# auxboxshield1_52.net
KiCad netlist of a schematic drawn in EAGLE
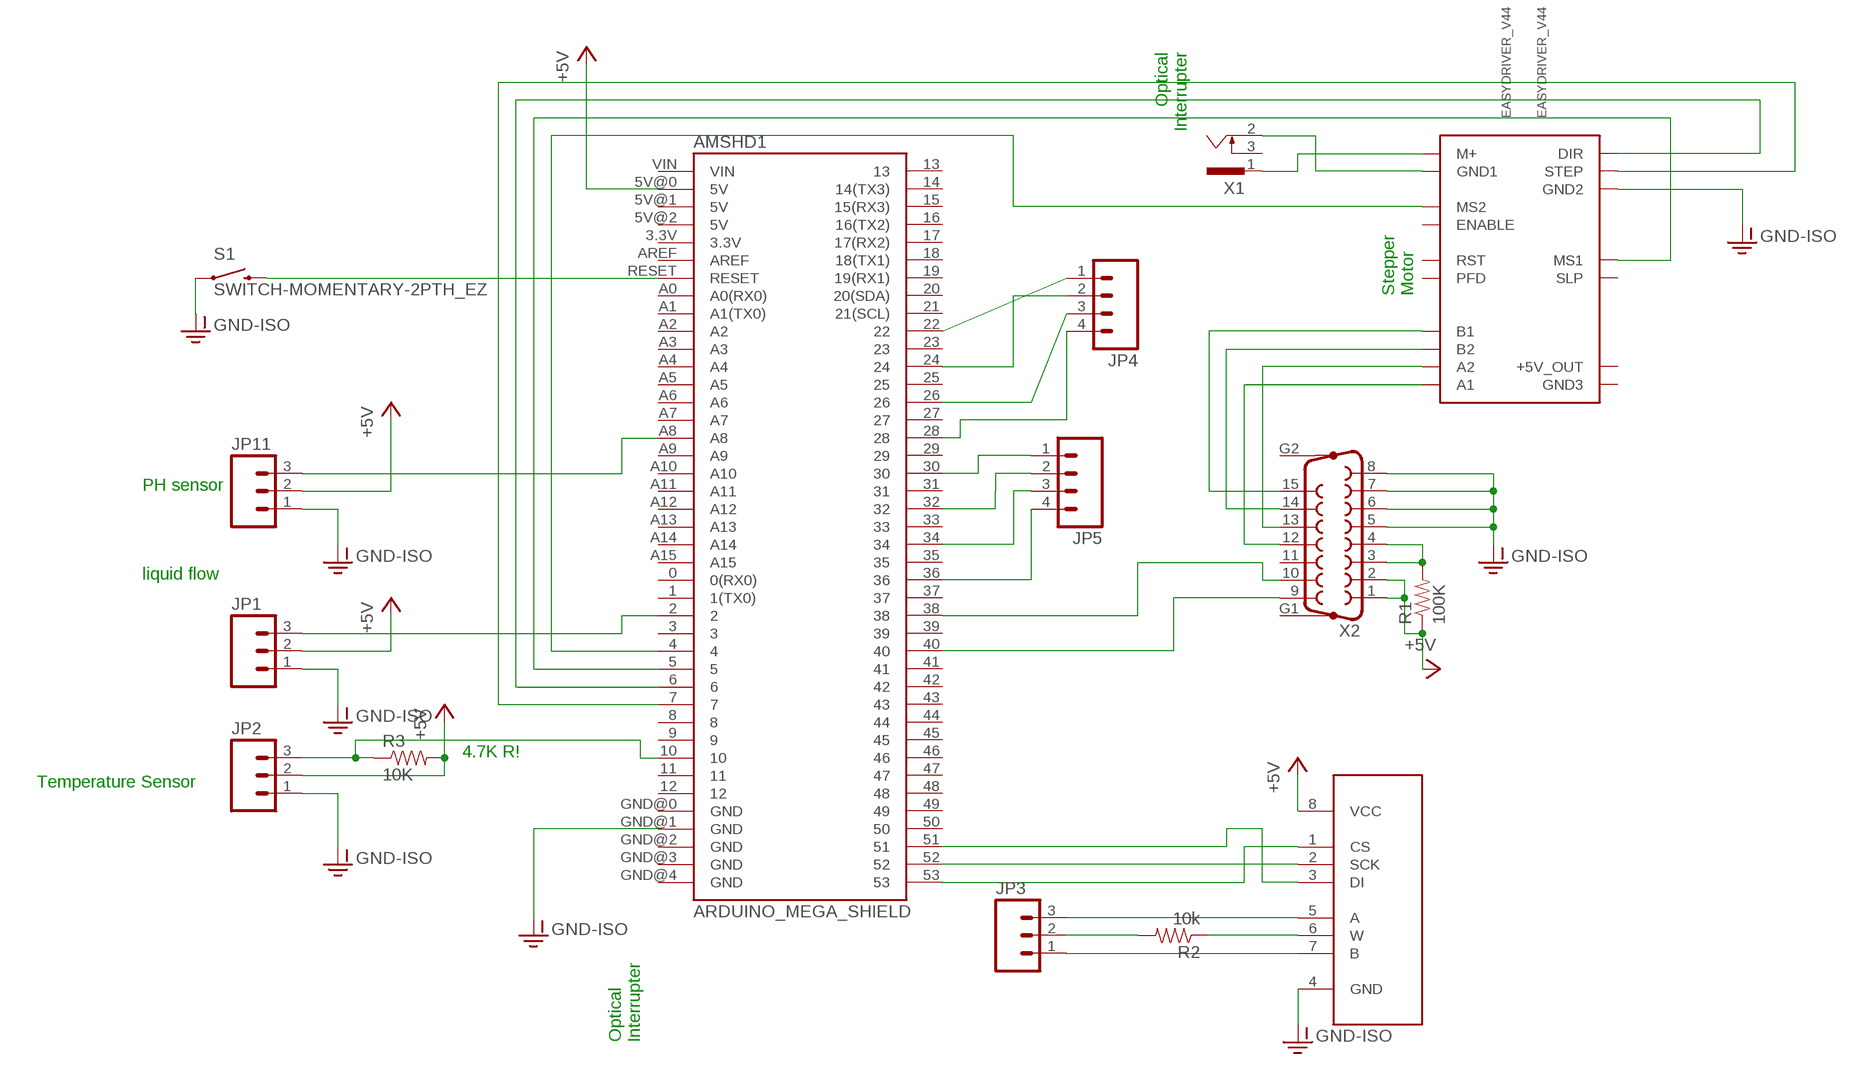
[diagram p0: schematic, sheet 1]

(export (version "E")
  (design (tool "Eeschema 10.0.6"))
  (components
    (comp (ref "AMSHD1")
      (value "ARDUINO_MEGA_SHIELD")
      (footprint "eagle-import:ARDUINO_MEGA_SHIELD")
      (libsource (lib "eagle-import") (part "ARDUINO_MEGA_SHIELD"))
    )
    (comp (ref "EASYDRIVER_V44")
      (value "EASYDRIVER_V44")
      (footprint "eagle-import:EASYDRIVER_V44")
      (libsource (lib "eagle-import") (part "EASYDRIVER_V44"))
    )
    (comp (ref "JP1")
      (value "M03POLAR")
      (footprint "eagle-import:MOLEX-1X3")
      (libsource (lib "eagle-import") (part "M03POLAR"))
    )
    (comp (ref "JP2")
      (value "M03POLAR")
      (footprint "eagle-import:MOLEX-1X3")
      (libsource (lib "eagle-import") (part "M03POLAR"))
    )
    (comp (ref "JP3")
      (value "M03POLAR")
      (footprint "eagle-import:MOLEX-1X3")
      (libsource (lib "eagle-import") (part "M03POLAR"))
    )
    (comp (ref "JP4")
      (value "M04POLAR")
      (footprint "eagle-import:MOLEX-1X4")
      (libsource (lib "eagle-import") (part "M04POLAR"))
    )
    (comp (ref "JP5")
      (value "M04POLAR")
      (footprint "eagle-import:MOLEX-1X4")
      (libsource (lib "eagle-import") (part "M04POLAR"))
    )
    (comp (ref "JP11")
      (value "M03POLAR")
      (footprint "eagle-import:MOLEX-1X3")
      (libsource (lib "eagle-import") (part "M03POLAR"))
    )
    (comp (ref "R1")
      (value "100K")
      (footprint "eagle-import:AXIAL-0.3")
      (libsource (lib "eagle-import") (part "100KOHM-1/4W-5%(PTH)"))
    )
    (comp (ref "R2")
      (value "10k")
      (footprint "eagle-import:AXIAL-0.3")
      (libsource (lib "eagle-import") (part "10KOHM-1/4W-1%(PTH)HORIZ"))
    )
    (comp (ref "R3")
      (value "10K")
      (footprint "eagle-import:AXIAL-0.3")
      (libsource (lib "eagle-import") (part "10OHM-1/4W-5%(PTH)"))
    )
    (comp (ref "S1")
      (value "SWITCH-MOMENTARY-2PTH_EZ")
      (footprint "eagle-import:TACTILE-PTH-EZ")
      (libsource (lib "eagle-import") (part "SWITCH-MOMENTARY-2PTH_EZ"))
    )
    (comp (ref "U2")
      (value "MCP41XXXDIL")
      (footprint "eagle-import:DIL-08")
      (libsource (lib "eagle-import") (part "MCP41XXXDIL"))
    )
    (comp (ref "X1")
      (value "SCD-014A")
      (footprint "eagle-import:SCD-014-A")
      (libsource (lib "eagle-import") (part "SCD-014A"))
    )
    (comp (ref "X2")
      (value "F15VP")
      (footprint "eagle-import:F15VP")
      (libsource (lib "eagle-import") (part "F15VP"))
    )
  )
  (nets
    (net (code "1") (name "+5V") (class "Default")
      (node (ref "AMSHD1") (pin "5V@0") (pinfunction "5V_5V@0") (pintype "bidirectional"))
      (node (ref "JP1") (pin "2") (pinfunction "2_2") (pintype "passive"))
      (node (ref "JP11") (pin "2") (pinfunction "2_2") (pintype "passive"))
      (node (ref "JP2") (pin "2") (pinfunction "2_2") (pintype "passive"))
      (node (ref "R1") (pin "P$1") (pinfunction "1_P$1") (pintype "passive"))
      (node (ref "R3") (pin "P$2") (pinfunction "2_P$2") (pintype "passive"))
      (node (ref "U2") (pin "8") (pinfunction "VCC_8") (pintype "bidirectional"))
      (node (ref "X2") (pin "1") (pinfunction "1_1") (pintype "passive"))
      (node (ref "X2") (pin "2") (pinfunction "2_2") (pintype "passive"))
    )
    (net (code "2") (name "GND-ISO") (class "Default")
      (node (ref "AMSHD1") (pin "GND@1") (pinfunction "GND_GND@1") (pintype "bidirectional"))
      (node (ref "EASYDRIVER_V44") (pin "GND2") (pinfunction "GND2_GND2") (pintype "bidirectional"))
      (node (ref "JP1") (pin "1") (pinfunction "1_1") (pintype "passive"))
      (node (ref "JP11") (pin "1") (pinfunction "1_1") (pintype "passive"))
      (node (ref "JP2") (pin "1") (pinfunction "1_1") (pintype "passive"))
      (node (ref "S1") (pin "1") (pinfunction "1_1") (pintype "passive"))
      (node (ref "U2") (pin "4") (pinfunction "GND_4") (pintype "bidirectional"))
      (node (ref "X2") (pin "5") (pinfunction "5_5") (pintype "passive"))
      (node (ref "X2") (pin "6") (pinfunction "6_6") (pintype "passive"))
      (node (ref "X2") (pin "7") (pinfunction "7_7") (pintype "passive"))
      (node (ref "X2") (pin "8") (pinfunction "8_8") (pintype "passive"))
    )
    (net (code "3") (name "Net-(AMSHD1-Pad2)") (class "Default")
      (node (ref "AMSHD1") (pin "2") (pinfunction "2_2") (pintype "bidirectional"))
      (node (ref "JP1") (pin "3") (pinfunction "3_3") (pintype "passive"))
    )
    (net (code "4") (name "Net-(AMSHD1-Pad4)") (class "Default")
      (node (ref "AMSHD1") (pin "4") (pinfunction "4_4") (pintype "bidirectional"))
      (node (ref "EASYDRIVER_V44") (pin "MS2") (pinfunction "MS2_MS2") (pintype "bidirectional"))
    )
    (net (code "5") (name "Net-(AMSHD1-Pad5)") (class "Default")
      (node (ref "AMSHD1") (pin "5") (pinfunction "5_5") (pintype "bidirectional"))
      (node (ref "EASYDRIVER_V44") (pin "MS1") (pinfunction "MS1_MS1") (pintype "bidirectional"))
    )
    (net (code "6") (name "Net-(AMSHD1-Pad6)") (class "Default")
      (node (ref "AMSHD1") (pin "6") (pinfunction "6_6") (pintype "bidirectional"))
      (node (ref "EASYDRIVER_V44") (pin "DIR") (pinfunction "DIR_DIR") (pintype "bidirectional"))
    )
    (net (code "7") (name "Net-(AMSHD1-Pad7)") (class "Default")
      (node (ref "AMSHD1") (pin "7") (pinfunction "7_7") (pintype "bidirectional"))
      (node (ref "EASYDRIVER_V44") (pin "STEP") (pinfunction "STEP_STEP") (pintype "bidirectional"))
    )
    (net (code "8") (name "Net-(AMSHD1-Pad22)") (class "Default")
      (node (ref "AMSHD1") (pin "22") (pinfunction "22_22") (pintype "bidirectional"))
      (node (ref "JP4") (pin "1") (pinfunction "1_1") (pintype "passive"))
    )
    (net (code "9") (name "Net-(AMSHD1-Pad24)") (class "Default")
      (node (ref "AMSHD1") (pin "24") (pinfunction "24_24") (pintype "bidirectional"))
      (node (ref "JP4") (pin "2") (pinfunction "2_2") (pintype "passive"))
    )
    (net (code "10") (name "Net-(AMSHD1-Pad26)") (class "Default")
      (node (ref "AMSHD1") (pin "26") (pinfunction "26_26") (pintype "bidirectional"))
      (node (ref "JP4") (pin "3") (pinfunction "3_3") (pintype "passive"))
    )
    (net (code "11") (name "Net-(AMSHD1-Pad28)") (class "Default")
      (node (ref "AMSHD1") (pin "28") (pinfunction "28_28") (pintype "bidirectional"))
      (node (ref "JP4") (pin "4") (pinfunction "4_4") (pintype "passive"))
    )
    (net (code "12") (name "Net-(AMSHD1-Pad30)") (class "Default")
      (node (ref "AMSHD1") (pin "30") (pinfunction "30_30") (pintype "bidirectional"))
      (node (ref "JP5") (pin "1") (pinfunction "1_1") (pintype "passive"))
    )
    (net (code "13") (name "Net-(AMSHD1-Pad32)") (class "Default")
      (node (ref "AMSHD1") (pin "32") (pinfunction "32_32") (pintype "bidirectional"))
      (node (ref "JP5") (pin "2") (pinfunction "2_2") (pintype "passive"))
    )
    (net (code "14") (name "Net-(AMSHD1-Pad34)") (class "Default")
      (node (ref "AMSHD1") (pin "34") (pinfunction "34_34") (pintype "bidirectional"))
      (node (ref "JP5") (pin "3") (pinfunction "3_3") (pintype "passive"))
    )
    (net (code "15") (name "Net-(AMSHD1-Pad36)") (class "Default")
      (node (ref "AMSHD1") (pin "36") (pinfunction "36_36") (pintype "bidirectional"))
      (node (ref "JP5") (pin "4") (pinfunction "4_4") (pintype "passive"))
    )
    (net (code "16") (name "Net-(AMSHD1-Pad38)") (class "Default")
      (node (ref "AMSHD1") (pin "38") (pinfunction "38_38") (pintype "bidirectional"))
      (node (ref "X2") (pin "10") (pinfunction "10_10") (pintype "passive"))
    )
    (net (code "17") (name "Net-(AMSHD1-Pad40)") (class "Default")
      (node (ref "AMSHD1") (pin "40") (pinfunction "40_40") (pintype "bidirectional"))
      (node (ref "X2") (pin "9") (pinfunction "9_9") (pintype "passive"))
    )
    (net (code "18") (name "Net-(AMSHD1-PadA8)") (class "Default")
      (node (ref "AMSHD1") (pin "A8") (pinfunction "A8_A8") (pintype "bidirectional"))
      (node (ref "JP11") (pin "3") (pinfunction "3_3") (pintype "passive"))
    )
    (net (code "19") (name "Net-(EASYDRIVER_V44-PadA1)") (class "Default")
      (node (ref "EASYDRIVER_V44") (pin "A1") (pinfunction "A1_A1") (pintype "bidirectional"))
      (node (ref "X2") (pin "12") (pinfunction "12_12") (pintype "passive"))
    )
    (net (code "20") (name "Net-(EASYDRIVER_V44-PadA2)") (class "Default")
      (node (ref "EASYDRIVER_V44") (pin "A2") (pinfunction "A2_A2") (pintype "bidirectional"))
      (node (ref "X2") (pin "13") (pinfunction "13_13") (pintype "passive"))
    )
    (net (code "21") (name "Net-(EASYDRIVER_V44-PadB1)") (class "Default")
      (node (ref "EASYDRIVER_V44") (pin "B1") (pinfunction "B1_B1") (pintype "bidirectional"))
      (node (ref "X2") (pin "15") (pinfunction "15_15") (pintype "passive"))
    )
    (net (code "22") (name "Net-(EASYDRIVER_V44-PadB2)") (class "Default")
      (node (ref "EASYDRIVER_V44") (pin "B2") (pinfunction "B2_B2") (pintype "bidirectional"))
      (node (ref "X2") (pin "14") (pinfunction "14_14") (pintype "passive"))
    )
    (net (code "23") (name "Net-(EASYDRIVER_V44-PadGND1)") (class "Default")
      (node (ref "EASYDRIVER_V44") (pin "GND1") (pinfunction "GND1_GND1") (pintype "bidirectional"))
      (node (ref "X1") (pin "2") (pinfunction "2_2") (pintype "passive"))
    )
    (net (code "24") (name "Net-(EASYDRIVER_V44-PadM+)") (class "Default")
      (node (ref "EASYDRIVER_V44") (pin "M+") (pinfunction "M+_M+") (pintype "bidirectional"))
      (node (ref "X1") (pin "1") (pinfunction "1_1") (pintype "passive"))
    )
    (net (code "25") (name "Net-(R1-2)") (class "Default")
      (node (ref "R1") (pin "P$2") (pinfunction "2_P$2") (pintype "passive"))
      (node (ref "X2") (pin "3") (pinfunction "3_3") (pintype "passive"))
      (node (ref "X2") (pin "4") (pinfunction "4_4") (pintype "passive"))
    )
    (net (code "26") (name "Net-(R2-1)") (class "Default")
      (node (ref "R2") (pin "P$1") (pinfunction "1_P$1") (pintype "passive"))
      (node (ref "U2") (pin "6") (pinfunction "W_6") (pintype "bidirectional"))
    )
    (net (code "27") (name "Net-(R2-2)") (class "Default")
      (node (ref "JP3") (pin "2") (pinfunction "2_2") (pintype "passive"))
      (node (ref "R2") (pin "P$2") (pinfunction "2_P$2") (pintype "passive"))
    )
    (net (code "28") (name "Net-(R3-1)") (class "Default")
      (node (ref "AMSHD1") (pin "10") (pinfunction "10_10") (pintype "bidirectional"))
      (node (ref "JP2") (pin "3") (pinfunction "3_3") (pintype "passive"))
      (node (ref "R3") (pin "P$1") (pinfunction "1_P$1") (pintype "passive"))
    )
    (net (code "29") (name "Net-(S1-2)") (class "Default")
      (node (ref "AMSHD1") (pin "RESET") (pinfunction "RESET_RESET") (pintype "bidirectional"))
      (node (ref "S1") (pin "3") (pinfunction "2_3") (pintype "passive"))
    )
    (net (code "30") (name "Net-(U2-A)") (class "Default")
      (node (ref "JP3") (pin "3") (pinfunction "3_3") (pintype "passive"))
      (node (ref "U2") (pin "5") (pinfunction "A_5") (pintype "bidirectional"))
    )
    (net (code "31") (name "Net-(U2-B)") (class "Default")
      (node (ref "JP3") (pin "1") (pinfunction "1_1") (pintype "passive"))
      (node (ref "U2") (pin "7") (pinfunction "B_7") (pintype "bidirectional"))
    )
    (net (code "32") (name "Net-(U2-CS)") (class "Default")
      (node (ref "AMSHD1") (pin "53") (pinfunction "53_53") (pintype "bidirectional"))
      (node (ref "U2") (pin "1") (pinfunction "CS_1") (pintype "bidirectional"))
    )
    (net (code "33") (name "Net-(U2-DI)") (class "Default")
      (node (ref "AMSHD1") (pin "51") (pinfunction "51_51") (pintype "bidirectional"))
      (node (ref "U2") (pin "3") (pinfunction "DI_3") (pintype "bidirectional"))
    )
    (net (code "34") (name "Net-(U2-SCK)") (class "Default")
      (node (ref "AMSHD1") (pin "52") (pinfunction "52_52") (pintype "bidirectional"))
      (node (ref "U2") (pin "2") (pinfunction "SCK_2") (pintype "bidirectional"))
    )
    (net (code "35") (name "unconnected-(AMSHD1-0(RX0)-Pad0)") (class "Default")
      (node (ref "AMSHD1") (pin "0") (pinfunction "0(RX0)_0") (pintype "bidirectional"))
    )
    (net (code "36") (name "unconnected-(AMSHD1-1(TX0)-Pad1)") (class "Default")
      (node (ref "AMSHD1") (pin "1") (pinfunction "1(TX0)_1") (pintype "bidirectional"))
    )
    (net (code "37") (name "unconnected-(AMSHD1-5V-Pad5V@1)") (class "Default")
      (node (ref "AMSHD1") (pin "5V@1") (pinfunction "5V_5V@1") (pintype "bidirectional"))
    )
    (net (code "38") (name "unconnected-(AMSHD1-5V-Pad5V@2)") (class "Default")
      (node (ref "AMSHD1") (pin "5V@2") (pinfunction "5V_5V@2") (pintype "bidirectional"))
    )
    (net (code "39") (name "unconnected-(AMSHD1-14(TX3)-Pad14)") (class "Default")
      (node (ref "AMSHD1") (pin "14") (pinfunction "14(TX3)_14") (pintype "bidirectional"))
    )
    (net (code "40") (name "unconnected-(AMSHD1-15(RX3)-Pad15)") (class "Default")
      (node (ref "AMSHD1") (pin "15") (pinfunction "15(RX3)_15") (pintype "bidirectional"))
    )
    (net (code "41") (name "unconnected-(AMSHD1-16(TX2)-Pad16)") (class "Default")
      (node (ref "AMSHD1") (pin "16") (pinfunction "16(TX2)_16") (pintype "bidirectional"))
    )
    (net (code "42") (name "unconnected-(AMSHD1-17(RX2)-Pad17)") (class "Default")
      (node (ref "AMSHD1") (pin "17") (pinfunction "17(RX2)_17") (pintype "bidirectional"))
    )
    (net (code "43") (name "unconnected-(AMSHD1-18(TX1)-Pad18)") (class "Default")
      (node (ref "AMSHD1") (pin "18") (pinfunction "18(TX1)_18") (pintype "bidirectional"))
    )
    (net (code "44") (name "unconnected-(AMSHD1-19(RX1)-Pad19)") (class "Default")
      (node (ref "AMSHD1") (pin "19") (pinfunction "19(RX1)_19") (pintype "bidirectional"))
    )
    (net (code "45") (name "unconnected-(AMSHD1-20(SDA)-Pad20)") (class "Default")
      (node (ref "AMSHD1") (pin "20") (pinfunction "20(SDA)_20") (pintype "bidirectional"))
    )
    (net (code "46") (name "unconnected-(AMSHD1-21(SCL)-Pad21)") (class "Default")
      (node (ref "AMSHD1") (pin "21") (pinfunction "21(SCL)_21") (pintype "bidirectional"))
    )
    (net (code "47") (name "unconnected-(AMSHD1-A0(RX0)-PadA0)") (class "Default")
      (node (ref "AMSHD1") (pin "A0") (pinfunction "A0(RX0)_A0") (pintype "bidirectional"))
    )
    (net (code "48") (name "unconnected-(AMSHD1-A1(TX0)-PadA1)") (class "Default")
      (node (ref "AMSHD1") (pin "A1") (pinfunction "A1(TX0)_A1") (pintype "bidirectional"))
    )
    (net (code "49") (name "unconnected-(AMSHD1-GND-PadGND@0)") (class "Default")
      (node (ref "AMSHD1") (pin "GND@0") (pinfunction "GND_GND@0") (pintype "bidirectional"))
    )
    (net (code "50") (name "unconnected-(AMSHD1-GND-PadGND@2)") (class "Default")
      (node (ref "AMSHD1") (pin "GND@2") (pinfunction "GND_GND@2") (pintype "bidirectional"))
    )
    (net (code "51") (name "unconnected-(AMSHD1-GND-PadGND@3)") (class "Default")
      (node (ref "AMSHD1") (pin "GND@3") (pinfunction "GND_GND@3") (pintype "bidirectional"))
    )
    (net (code "52") (name "unconnected-(AMSHD1-GND-PadGND@4)") (class "Default")
      (node (ref "AMSHD1") (pin "GND@4") (pinfunction "GND_GND@4") (pintype "bidirectional"))
    )
    (net (code "53") (name "unconnected-(AMSHD1-Pad3)") (class "Default")
      (node (ref "AMSHD1") (pin "3") (pinfunction "3_3") (pintype "bidirectional"))
    )
    (net (code "54") (name "unconnected-(AMSHD1-Pad3.3V)") (class "Default")
      (node (ref "AMSHD1") (pin "3.3V") (pinfunction "3.3V_3.3V") (pintype "bidirectional"))
    )
    (net (code "55") (name "unconnected-(AMSHD1-Pad8)") (class "Default")
      (node (ref "AMSHD1") (pin "8") (pinfunction "8_8") (pintype "bidirectional"))
    )
    (net (code "56") (name "unconnected-(AMSHD1-Pad9)") (class "Default")
      (node (ref "AMSHD1") (pin "9") (pinfunction "9_9") (pintype "bidirectional"))
    )
    (net (code "57") (name "unconnected-(AMSHD1-Pad11)") (class "Default")
      (node (ref "AMSHD1") (pin "11") (pinfunction "11_11") (pintype "bidirectional"))
    )
    (net (code "58") (name "unconnected-(AMSHD1-Pad12)") (class "Default")
      (node (ref "AMSHD1") (pin "12") (pinfunction "12_12") (pintype "bidirectional"))
    )
    (net (code "59") (name "unconnected-(AMSHD1-Pad13)") (class "Default")
      (node (ref "AMSHD1") (pin "13") (pinfunction "13_13") (pintype "bidirectional"))
    )
    (net (code "60") (name "unconnected-(AMSHD1-Pad23)") (class "Default")
      (node (ref "AMSHD1") (pin "23") (pinfunction "23_23") (pintype "bidirectional"))
    )
    (net (code "61") (name "unconnected-(AMSHD1-Pad25)") (class "Default")
      (node (ref "AMSHD1") (pin "25") (pinfunction "25_25") (pintype "bidirectional"))
    )
    (net (code "62") (name "unconnected-(AMSHD1-Pad27)") (class "Default")
      (node (ref "AMSHD1") (pin "27") (pinfunction "27_27") (pintype "bidirectional"))
    )
    (net (code "63") (name "unconnected-(AMSHD1-Pad29)") (class "Default")
      (node (ref "AMSHD1") (pin "29") (pinfunction "29_29") (pintype "bidirectional"))
    )
    (net (code "64") (name "unconnected-(AMSHD1-Pad31)") (class "Default")
      (node (ref "AMSHD1") (pin "31") (pinfunction "31_31") (pintype "bidirectional"))
    )
    (net (code "65") (name "unconnected-(AMSHD1-Pad33)") (class "Default")
      (node (ref "AMSHD1") (pin "33") (pinfunction "33_33") (pintype "bidirectional"))
    )
    (net (code "66") (name "unconnected-(AMSHD1-Pad35)") (class "Default")
      (node (ref "AMSHD1") (pin "35") (pinfunction "35_35") (pintype "bidirectional"))
    )
    (net (code "67") (name "unconnected-(AMSHD1-Pad37)") (class "Default")
      (node (ref "AMSHD1") (pin "37") (pinfunction "37_37") (pintype "bidirectional"))
    )
    (net (code "68") (name "unconnected-(AMSHD1-Pad39)") (class "Default")
      (node (ref "AMSHD1") (pin "39") (pinfunction "39_39") (pintype "bidirectional"))
    )
    (net (code "69") (name "unconnected-(AMSHD1-Pad41)") (class "Default")
      (node (ref "AMSHD1") (pin "41") (pinfunction "41_41") (pintype "bidirectional"))
    )
    (net (code "70") (name "unconnected-(AMSHD1-Pad42)") (class "Default")
      (node (ref "AMSHD1") (pin "42") (pinfunction "42_42") (pintype "bidirectional"))
    )
    (net (code "71") (name "unconnected-(AMSHD1-Pad43)") (class "Default")
      (node (ref "AMSHD1") (pin "43") (pinfunction "43_43") (pintype "bidirectional"))
    )
    (net (code "72") (name "unconnected-(AMSHD1-Pad44)") (class "Default")
      (node (ref "AMSHD1") (pin "44") (pinfunction "44_44") (pintype "bidirectional"))
    )
    (net (code "73") (name "unconnected-(AMSHD1-Pad45)") (class "Default")
      (node (ref "AMSHD1") (pin "45") (pinfunction "45_45") (pintype "bidirectional"))
    )
    (net (code "74") (name "unconnected-(AMSHD1-Pad46)") (class "Default")
      (node (ref "AMSHD1") (pin "46") (pinfunction "46_46") (pintype "bidirectional"))
    )
    (net (code "75") (name "unconnected-(AMSHD1-Pad47)") (class "Default")
      (node (ref "AMSHD1") (pin "47") (pinfunction "47_47") (pintype "bidirectional"))
    )
    (net (code "76") (name "unconnected-(AMSHD1-Pad48)") (class "Default")
      (node (ref "AMSHD1") (pin "48") (pinfunction "48_48") (pintype "bidirectional"))
    )
    (net (code "77") (name "unconnected-(AMSHD1-Pad49)") (class "Default")
      (node (ref "AMSHD1") (pin "49") (pinfunction "49_49") (pintype "bidirectional"))
    )
    (net (code "78") (name "unconnected-(AMSHD1-Pad50)") (class "Default")
      (node (ref "AMSHD1") (pin "50") (pinfunction "50_50") (pintype "bidirectional"))
    )
    (net (code "79") (name "unconnected-(AMSHD1-PadA2)") (class "Default")
      (node (ref "AMSHD1") (pin "A2") (pinfunction "A2_A2") (pintype "bidirectional"))
    )
    (net (code "80") (name "unconnected-(AMSHD1-PadA3)") (class "Default")
      (node (ref "AMSHD1") (pin "A3") (pinfunction "A3_A3") (pintype "bidirectional"))
    )
    (net (code "81") (name "unconnected-(AMSHD1-PadA4)") (class "Default")
      (node (ref "AMSHD1") (pin "A4") (pinfunction "A4_A4") (pintype "bidirectional"))
    )
    (net (code "82") (name "unconnected-(AMSHD1-PadA5)") (class "Default")
      (node (ref "AMSHD1") (pin "A5") (pinfunction "A5_A5") (pintype "bidirectional"))
    )
    (net (code "83") (name "unconnected-(AMSHD1-PadA6)") (class "Default")
      (node (ref "AMSHD1") (pin "A6") (pinfunction "A6_A6") (pintype "bidirectional"))
    )
    (net (code "84") (name "unconnected-(AMSHD1-PadA7)") (class "Default")
      (node (ref "AMSHD1") (pin "A7") (pinfunction "A7_A7") (pintype "bidirectional"))
    )
    (net (code "85") (name "unconnected-(AMSHD1-PadA9)") (class "Default")
      (node (ref "AMSHD1") (pin "A9") (pinfunction "A9_A9") (pintype "bidirectional"))
    )
    (net (code "86") (name "unconnected-(AMSHD1-PadA10)") (class "Default")
      (node (ref "AMSHD1") (pin "A10") (pinfunction "A10_A10") (pintype "bidirectional"))
    )
    (net (code "87") (name "unconnected-(AMSHD1-PadA11)") (class "Default")
      (node (ref "AMSHD1") (pin "A11") (pinfunction "A11_A11") (pintype "bidirectional"))
    )
    (net (code "88") (name "unconnected-(AMSHD1-PadA12)") (class "Default")
      (node (ref "AMSHD1") (pin "A12") (pinfunction "A12_A12") (pintype "bidirectional"))
    )
    (net (code "89") (name "unconnected-(AMSHD1-PadA13)") (class "Default")
      (node (ref "AMSHD1") (pin "A13") (pinfunction "A13_A13") (pintype "bidirectional"))
    )
    (net (code "90") (name "unconnected-(AMSHD1-PadA14)") (class "Default")
      (node (ref "AMSHD1") (pin "A14") (pinfunction "A14_A14") (pintype "bidirectional"))
    )
    (net (code "91") (name "unconnected-(AMSHD1-PadA15)") (class "Default")
      (node (ref "AMSHD1") (pin "A15") (pinfunction "A15_A15") (pintype "bidirectional"))
    )
    (net (code "92") (name "unconnected-(AMSHD1-PadAREF)") (class "Default")
      (node (ref "AMSHD1") (pin "AREF") (pinfunction "AREF_AREF") (pintype "bidirectional"))
    )
    (net (code "93") (name "unconnected-(AMSHD1-PadVIN)") (class "Default")
      (node (ref "AMSHD1") (pin "VIN") (pinfunction "VIN_VIN") (pintype "bidirectional"))
    )
    (net (code "94") (name "unconnected-(EASYDRIVER_V44-+5V_OUT-PadP$11)") (class "Default")
      (node (ref "EASYDRIVER_V44") (pin "P$11") (pinfunction "+5V_OUT_P$11") (pintype "bidirectional"))
    )
    (net (code "95") (name "unconnected-(EASYDRIVER_V44-PadENABLE)") (class "Default")
      (node (ref "EASYDRIVER_V44") (pin "ENABLE") (pinfunction "ENABLE_ENABLE") (pintype "bidirectional"))
    )
    (net (code "96") (name "unconnected-(EASYDRIVER_V44-PadGND3)") (class "Default")
      (node (ref "EASYDRIVER_V44") (pin "GND3") (pinfunction "GND3_GND3") (pintype "bidirectional"))
    )
    (net (code "97") (name "unconnected-(EASYDRIVER_V44-PadPFD)") (class "Default")
      (node (ref "EASYDRIVER_V44") (pin "PFD") (pinfunction "PFD_PFD") (pintype "bidirectional"))
    )
    (net (code "98") (name "unconnected-(EASYDRIVER_V44-PadRST)") (class "Default")
      (node (ref "EASYDRIVER_V44") (pin "RST") (pinfunction "RST_RST") (pintype "bidirectional"))
    )
    (net (code "99") (name "unconnected-(EASYDRIVER_V44-SLP-PadSLEEP)") (class "Default")
      (node (ref "EASYDRIVER_V44") (pin "SLEEP") (pinfunction "SLP_SLEEP") (pintype "bidirectional"))
    )
    (net (code "100") (name "unconnected-(X1-Pad3)") (class "Default")
      (node (ref "X1") (pin "3") (pinfunction "3_3") (pintype "passive"))
    )
    (net (code "101") (name "unconnected-(X2-Pad11)") (class "Default")
      (node (ref "X2") (pin "11") (pinfunction "11_11") (pintype "passive"))
    )
    (net (code "102") (name "unconnected-(X2-PadG1)") (class "Default")
      (node (ref "X2") (pin "G1") (pinfunction "G1_G1") (pintype "passive"))
    )
    (net (code "103") (name "unconnected-(X2-PadG2)") (class "Default")
      (node (ref "X2") (pin "G2") (pinfunction "G2_G2") (pintype "passive"))
    )
  )
)
